# usbdimmer-control-vertical.net
KiCad netlist of a schematic drawn in EAGLE
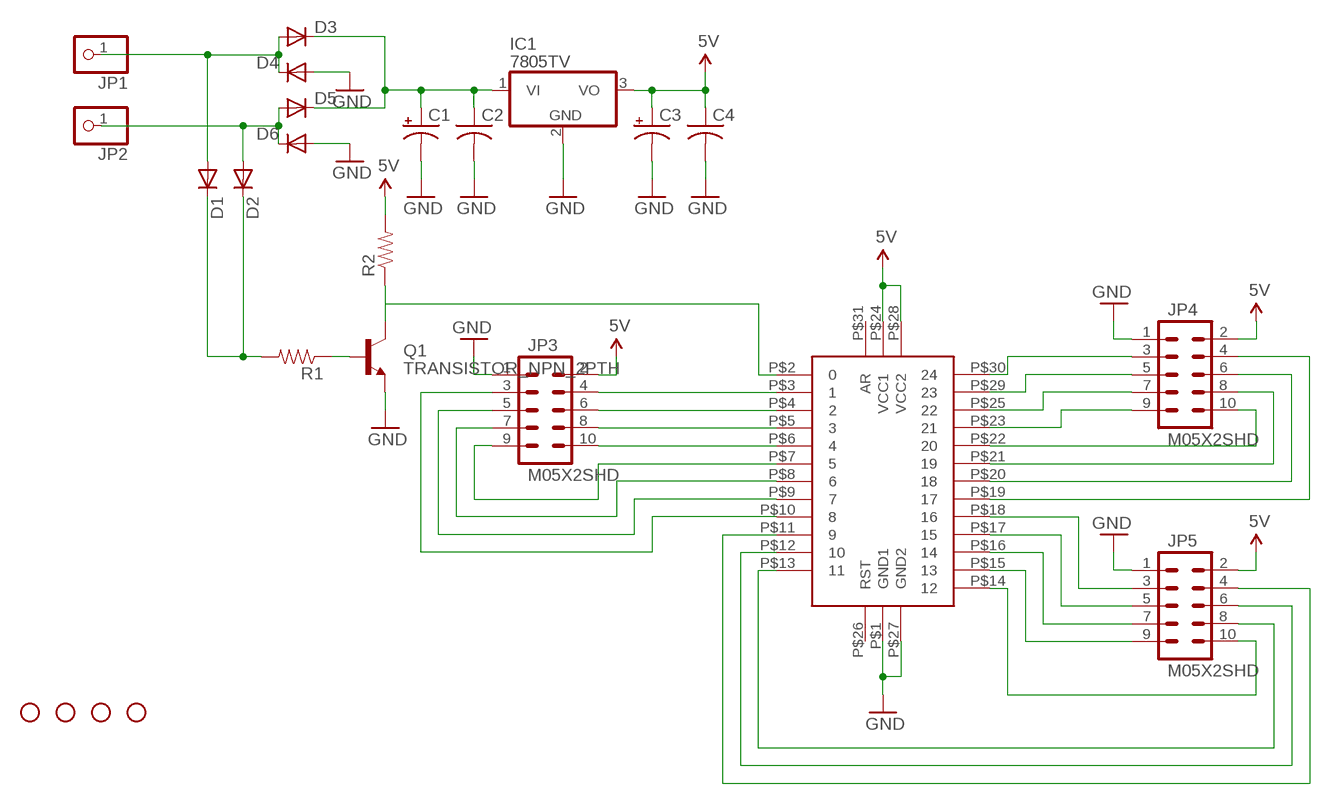
[diagram p0: schematic, sheet 1]

(export (version "E")
  (design (tool "Eeschema 10.0.6"))
  (components
    (comp (ref "C1")
      (value "CPOL-USE3.5-10")
      (footprint "eagle-import:E3,5-10")
      (libsource (lib "eagle-import") (part "CPOL-USE3.5-10"))
    )
    (comp (ref "C2")
      (value "C-US025-030X050")
      (footprint "eagle-import:C025-030X050")
      (libsource (lib "eagle-import") (part "C-US025-030X050"))
    )
    (comp (ref "C3")
      (value "CPOL-USE3.5-10")
      (footprint "eagle-import:E3,5-10")
      (libsource (lib "eagle-import") (part "CPOL-USE3.5-10"))
    )
    (comp (ref "C4")
      (value "C-US025-030X050")
      (footprint "eagle-import:C025-030X050")
      (libsource (lib "eagle-import") (part "C-US025-030X050"))
    )
    (comp (ref "D1")
      (value "DIODE1N4148")
      (footprint "eagle-import:DIODE-1N4148")
      (libsource (lib "eagle-import") (part "DIODE1N4148"))
    )
    (comp (ref "D2")
      (value "DIODE1N4148")
      (footprint "eagle-import:DIODE-1N4148")
      (libsource (lib "eagle-import") (part "DIODE1N4148"))
    )
    (comp (ref "D3")
      (value "DIODEPTH")
      (footprint "eagle-import:DIODE-1N4001")
      (libsource (lib "eagle-import") (part "DIODEPTH"))
    )
    (comp (ref "D4")
      (value "DIODEPTH")
      (footprint "eagle-import:DIODE-1N4001")
      (libsource (lib "eagle-import") (part "DIODEPTH"))
    )
    (comp (ref "D5")
      (value "DIODEPTH")
      (footprint "eagle-import:DIODE-1N4001")
      (libsource (lib "eagle-import") (part "DIODEPTH"))
    )
    (comp (ref "D6")
      (value "DIODEPTH")
      (footprint "eagle-import:DIODE-1N4001")
      (libsource (lib "eagle-import") (part "DIODEPTH"))
    )
    (comp (ref "IC1")
      (value "7805TV")
      (footprint "eagle-import:TO220V")
      (libsource (lib "eagle-import") (part "78TV05"))
    )
    (comp (ref "IC2")
      (value "TEENSY2")
      (footprint "eagle-import:TEENSY2")
      (libsource (lib "eagle-import") (part "TEENSY2"))
    )
    (comp (ref "JP1")
      (value "PINHD-1X1")
      (footprint "eagle-import:1X01")
      (libsource (lib "eagle-import") (part "PINHD-1X1"))
    )
    (comp (ref "JP2")
      (value "PINHD-1X1")
      (footprint "eagle-import:1X01")
      (libsource (lib "eagle-import") (part "PINHD-1X1"))
    )
    (comp (ref "JP3")
      (value "M05X2SHD")
      (footprint "eagle-import:2X5-SHROUDED")
      (libsource (lib "eagle-import") (part "M05X2SHD"))
    )
    (comp (ref "JP4")
      (value "M05X2SHD")
      (footprint "eagle-import:2X5-SHROUDED")
      (libsource (lib "eagle-import") (part "M05X2SHD"))
    )
    (comp (ref "JP5")
      (value "M05X2SHD")
      (footprint "eagle-import:2X5-SHROUDED")
      (libsource (lib "eagle-import") (part "M05X2SHD"))
    )
    (comp (ref "Q1")
      (value "TRANSISTOR_NPN_2PTH")
      (footprint "eagle-import:TO-92")
      (libsource (lib "eagle-import") (part "TRANSISTOR_NPN_2PTH"))
    )
    (comp (ref "R1")
      (value "RESISTORPTH-1/4W")
      (footprint "eagle-import:AXIAL-0.4")
      (libsource (lib "eagle-import") (part "RESISTORPTH-1/4W"))
    )
    (comp (ref "R2")
      (value "RESISTORPTH-1/4W")
      (footprint "eagle-import:AXIAL-0.4")
      (libsource (lib "eagle-import") (part "RESISTORPTH-1/4W"))
    )
    (comp (ref "STANDOFF1")
      (value "STAND-OFF")
      (footprint "eagle-import:STAND-OFF")
      (libsource (lib "eagle-import") (part "STAND-OFF"))
    )
    (comp (ref "STANDOFF2")
      (value "STAND-OFF")
      (footprint "eagle-import:STAND-OFF")
      (libsource (lib "eagle-import") (part "STAND-OFF"))
    )
    (comp (ref "STANDOFF3")
      (value "STAND-OFF")
      (footprint "eagle-import:STAND-OFF")
      (libsource (lib "eagle-import") (part "STAND-OFF"))
    )
    (comp (ref "STANDOFF4")
      (value "STAND-OFF")
      (footprint "eagle-import:STAND-OFF")
      (libsource (lib "eagle-import") (part "STAND-OFF"))
    )
  )
  (nets
    (net (code "1") (name "5V") (class "Default")
      (node (ref "C3") (pin "+") (pinfunction "+_+") (pintype "passive"))
      (node (ref "C4") (pin "1") (pinfunction "1_1") (pintype "passive"))
      (node (ref "IC1") (pin "3") (pinfunction "VO_3") (pintype "passive"))
      (node (ref "IC2") (pin "P$24") (pinfunction "VCC1_P$24") (pintype "bidirectional"))
      (node (ref "IC2") (pin "P$28") (pinfunction "VCC2_P$28") (pintype "bidirectional"))
      (node (ref "JP3") (pin "2") (pinfunction "2_2") (pintype "passive"))
      (node (ref "JP4") (pin "2") (pinfunction "2_2") (pintype "passive"))
      (node (ref "JP5") (pin "2") (pinfunction "2_2") (pintype "passive"))
      (node (ref "R2") (pin "P$2") (pinfunction "2_P$2") (pintype "passive"))
    )
    (net (code "2") (name "GND") (class "Default")
      (node (ref "C1") (pin "-") (pinfunction "-_-") (pintype "passive"))
      (node (ref "C2") (pin "2") (pinfunction "2_2") (pintype "passive"))
      (node (ref "C3") (pin "-") (pinfunction "-_-") (pintype "passive"))
      (node (ref "C4") (pin "2") (pinfunction "2_2") (pintype "passive"))
      (node (ref "D4") (pin "A") (pinfunction "A_A") (pintype "passive"))
      (node (ref "D6") (pin "A") (pinfunction "A_A") (pintype "passive"))
      (node (ref "IC1") (pin "2") (pinfunction "GND_2") (pintype "passive"))
      (node (ref "IC2") (pin "P$1") (pinfunction "GND1_P$1") (pintype "bidirectional"))
      (node (ref "IC2") (pin "P$27") (pinfunction "GND2_P$27") (pintype "bidirectional"))
      (node (ref "JP3") (pin "1") (pinfunction "1_1") (pintype "passive"))
      (node (ref "JP4") (pin "1") (pinfunction "1_1") (pintype "passive"))
      (node (ref "JP5") (pin "1") (pinfunction "1_1") (pintype "passive"))
      (node (ref "Q1") (pin "3") (pinfunction "E_3") (pintype "passive"))
    )
    (net (code "3") (name "Net-(D1-PadA)") (class "Default")
      (node (ref "D1") (pin "A") (pinfunction "A_A") (pintype "passive"))
      (node (ref "D3") (pin "A") (pinfunction "A_A") (pintype "passive"))
      (node (ref "D4") (pin "C") (pinfunction "C_C") (pintype "passive"))
      (node (ref "JP1") (pin "1") (pinfunction "1_1") (pintype "passive"))
    )
    (net (code "4") (name "Net-(D2-PadA)") (class "Default")
      (node (ref "D2") (pin "A") (pinfunction "A_A") (pintype "passive"))
      (node (ref "D5") (pin "A") (pinfunction "A_A") (pintype "passive"))
      (node (ref "D6") (pin "C") (pinfunction "C_C") (pintype "passive"))
      (node (ref "JP2") (pin "1") (pinfunction "1_1") (pintype "passive"))
    )
    (net (code "5") (name "Net-(IC1-VI)") (class "Default")
      (node (ref "C1") (pin "+") (pinfunction "+_+") (pintype "passive"))
      (node (ref "C2") (pin "1") (pinfunction "1_1") (pintype "passive"))
      (node (ref "D3") (pin "C") (pinfunction "C_C") (pintype "passive"))
      (node (ref "D5") (pin "C") (pinfunction "C_C") (pintype "passive"))
      (node (ref "IC1") (pin "1") (pinfunction "VI_1") (pintype "input"))
    )
    (net (code "6") (name "Net-(IC2-0)") (class "Default")
      (node (ref "IC2") (pin "P$2") (pinfunction "0_P$2") (pintype "bidirectional"))
      (node (ref "Q1") (pin "1") (pinfunction "C_1") (pintype "passive"))
      (node (ref "R2") (pin "P$1") (pinfunction "1_P$1") (pintype "passive"))
    )
    (net (code "7") (name "Net-(IC2-1)") (class "Default")
      (node (ref "IC2") (pin "P$3") (pinfunction "1_P$3") (pintype "bidirectional"))
      (node (ref "JP3") (pin "4") (pinfunction "4_4") (pintype "passive"))
    )
    (net (code "8") (name "Net-(IC2-2)") (class "Default")
      (node (ref "IC2") (pin "P$4") (pinfunction "2_P$4") (pintype "bidirectional"))
      (node (ref "JP3") (pin "6") (pinfunction "6_6") (pintype "passive"))
    )
    (net (code "9") (name "Net-(IC2-3)") (class "Default")
      (node (ref "IC2") (pin "P$5") (pinfunction "3_P$5") (pintype "bidirectional"))
      (node (ref "JP3") (pin "8") (pinfunction "8_8") (pintype "passive"))
    )
    (net (code "10") (name "Net-(IC2-4)") (class "Default")
      (node (ref "IC2") (pin "P$6") (pinfunction "4_P$6") (pintype "bidirectional"))
      (node (ref "JP3") (pin "10") (pinfunction "10_10") (pintype "passive"))
    )
    (net (code "11") (name "Net-(IC2-5)") (class "Default")
      (node (ref "IC2") (pin "P$7") (pinfunction "5_P$7") (pintype "bidirectional"))
      (node (ref "JP3") (pin "9") (pinfunction "9_9") (pintype "passive"))
    )
    (net (code "12") (name "Net-(IC2-6)") (class "Default")
      (node (ref "IC2") (pin "P$8") (pinfunction "6_P$8") (pintype "bidirectional"))
      (node (ref "JP3") (pin "7") (pinfunction "7_7") (pintype "passive"))
    )
    (net (code "13") (name "Net-(IC2-7)") (class "Default")
      (node (ref "IC2") (pin "P$9") (pinfunction "7_P$9") (pintype "bidirectional"))
      (node (ref "JP3") (pin "5") (pinfunction "5_5") (pintype "passive"))
    )
    (net (code "14") (name "Net-(IC2-8)") (class "Default")
      (node (ref "IC2") (pin "P$10") (pinfunction "8_P$10") (pintype "bidirectional"))
      (node (ref "JP3") (pin "3") (pinfunction "3_3") (pintype "passive"))
    )
    (net (code "15") (name "Net-(IC2-9)") (class "Default")
      (node (ref "IC2") (pin "P$11") (pinfunction "9_P$11") (pintype "bidirectional"))
      (node (ref "JP5") (pin "4") (pinfunction "4_4") (pintype "passive"))
    )
    (net (code "16") (name "Net-(IC2-10)") (class "Default")
      (node (ref "IC2") (pin "P$12") (pinfunction "10_P$12") (pintype "bidirectional"))
      (node (ref "JP5") (pin "6") (pinfunction "6_6") (pintype "passive"))
    )
    (net (code "17") (name "Net-(IC2-11)") (class "Default")
      (node (ref "IC2") (pin "P$13") (pinfunction "11_P$13") (pintype "bidirectional"))
      (node (ref "JP5") (pin "8") (pinfunction "8_8") (pintype "passive"))
    )
    (net (code "18") (name "Net-(IC2-12)") (class "Default")
      (node (ref "IC2") (pin "P$14") (pinfunction "12_P$14") (pintype "bidirectional"))
      (node (ref "JP5") (pin "10") (pinfunction "10_10") (pintype "passive"))
    )
    (net (code "19") (name "Net-(IC2-13)") (class "Default")
      (node (ref "IC2") (pin "P$15") (pinfunction "13_P$15") (pintype "bidirectional"))
      (node (ref "JP5") (pin "9") (pinfunction "9_9") (pintype "passive"))
    )
    (net (code "20") (name "Net-(IC2-14)") (class "Default")
      (node (ref "IC2") (pin "P$16") (pinfunction "14_P$16") (pintype "bidirectional"))
      (node (ref "JP5") (pin "7") (pinfunction "7_7") (pintype "passive"))
    )
    (net (code "21") (name "Net-(IC2-15)") (class "Default")
      (node (ref "IC2") (pin "P$17") (pinfunction "15_P$17") (pintype "bidirectional"))
      (node (ref "JP5") (pin "5") (pinfunction "5_5") (pintype "passive"))
    )
    (net (code "22") (name "Net-(IC2-16)") (class "Default")
      (node (ref "IC2") (pin "P$18") (pinfunction "16_P$18") (pintype "bidirectional"))
      (node (ref "JP5") (pin "3") (pinfunction "3_3") (pintype "passive"))
    )
    (net (code "23") (name "Net-(IC2-17)") (class "Default")
      (node (ref "IC2") (pin "P$19") (pinfunction "17_P$19") (pintype "bidirectional"))
      (node (ref "JP4") (pin "4") (pinfunction "4_4") (pintype "passive"))
    )
    (net (code "24") (name "Net-(IC2-18)") (class "Default")
      (node (ref "IC2") (pin "P$20") (pinfunction "18_P$20") (pintype "bidirectional"))
      (node (ref "JP4") (pin "6") (pinfunction "6_6") (pintype "passive"))
    )
    (net (code "25") (name "Net-(IC2-19)") (class "Default")
      (node (ref "IC2") (pin "P$21") (pinfunction "19_P$21") (pintype "bidirectional"))
      (node (ref "JP4") (pin "8") (pinfunction "8_8") (pintype "passive"))
    )
    (net (code "26") (name "Net-(IC2-20)") (class "Default")
      (node (ref "IC2") (pin "P$22") (pinfunction "20_P$22") (pintype "bidirectional"))
      (node (ref "JP4") (pin "10") (pinfunction "10_10") (pintype "passive"))
    )
    (net (code "27") (name "Net-(IC2-21)") (class "Default")
      (node (ref "IC2") (pin "P$23") (pinfunction "21_P$23") (pintype "bidirectional"))
      (node (ref "JP4") (pin "9") (pinfunction "9_9") (pintype "passive"))
    )
    (net (code "28") (name "Net-(IC2-22)") (class "Default")
      (node (ref "IC2") (pin "P$25") (pinfunction "22_P$25") (pintype "bidirectional"))
      (node (ref "JP4") (pin "7") (pinfunction "7_7") (pintype "passive"))
    )
    (net (code "29") (name "Net-(IC2-23)") (class "Default")
      (node (ref "IC2") (pin "P$29") (pinfunction "23_P$29") (pintype "bidirectional"))
      (node (ref "JP4") (pin "5") (pinfunction "5_5") (pintype "passive"))
    )
    (net (code "30") (name "Net-(IC2-24)") (class "Default")
      (node (ref "IC2") (pin "P$30") (pinfunction "24_P$30") (pintype "bidirectional"))
      (node (ref "JP4") (pin "3") (pinfunction "3_3") (pintype "passive"))
    )
    (net (code "31") (name "Net-(Q1-B)") (class "Default")
      (node (ref "Q1") (pin "2") (pinfunction "B_2") (pintype "passive"))
      (node (ref "R1") (pin "P$1") (pinfunction "1_P$1") (pintype "passive"))
    )
    (net (code "32") (name "Net-(R1-2)") (class "Default")
      (node (ref "D1") (pin "C") (pinfunction "C_C") (pintype "passive"))
      (node (ref "D2") (pin "C") (pinfunction "C_C") (pintype "passive"))
      (node (ref "R1") (pin "P$2") (pinfunction "2_P$2") (pintype "passive"))
    )
    (net (code "33") (name "unconnected-(IC2-AR-PadP$31)") (class "Default")
      (node (ref "IC2") (pin "P$31") (pinfunction "AR_P$31") (pintype "bidirectional"))
    )
    (net (code "34") (name "unconnected-(IC2-RST-PadP$26)") (class "Default")
      (node (ref "IC2") (pin "P$26") (pinfunction "RST_P$26") (pintype "bidirectional"))
    )
  )
)
